# class_ab.net
KiCad netlist of a schematic drawn in EAGLE
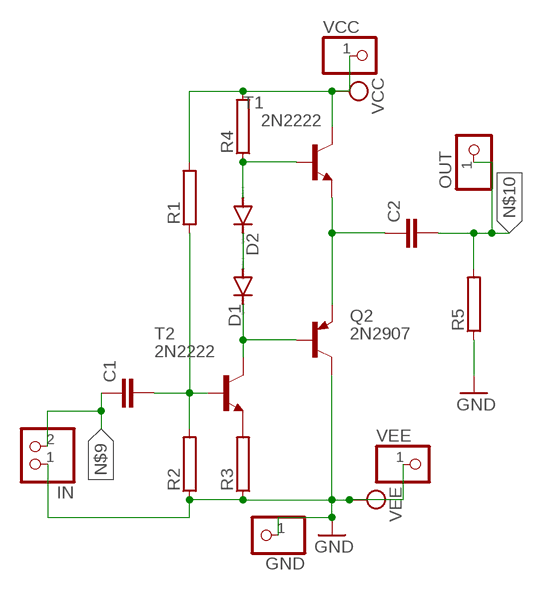
[diagram p0: schematic, sheet 1]

(export (version "E")
  (design (tool "Eeschema 10.0.6"))
  (components
    (comp (ref "C1")
      (value "C2,5-3")
      (footprint "eagle-import:C2.5-3")
      (libsource (lib "eagle-import") (part "C2,5-3"))
    )
    (comp (ref "C2")
      (value "C2,5-3")
      (footprint "eagle-import:C2.5-3")
      (libsource (lib "eagle-import") (part "C2,5-3"))
    )
    (comp (ref "D1")
      (value "1N4148DO35-7")
      (footprint "eagle-import:DO35-7")
      (libsource (lib "eagle-import") (part "1N4148DO35-7"))
    )
    (comp (ref "D2")
      (value "1N4148DO35-7")
      (footprint "eagle-import:DO35-7")
      (libsource (lib "eagle-import") (part "1N4148DO35-7"))
    )
    (comp (ref "GND")
      (value "PINHD-1X1")
      (footprint "eagle-import:1X01")
      (libsource (lib "eagle-import") (part "PINHD-1X1"))
    )
    (comp (ref "IN")
      (value "PINHD-1X2")
      (footprint "eagle-import:1X02")
      (libsource (lib "eagle-import") (part "PINHD-1X2"))
    )
    (comp (ref "OUT")
      (value "PINHD-1X1")
      (footprint "eagle-import:1X01")
      (libsource (lib "eagle-import") (part "PINHD-1X1"))
    )
    (comp (ref "Q2")
      (value "2N2907")
      (footprint "eagle-import:TO18")
      (libsource (lib "eagle-import") (part "2N2907"))
    )
    (comp (ref "R1")
      (value "RAC01")
      (footprint "eagle-import:AC01")
      (libsource (lib "eagle-import") (part "RAC01"))
    )
    (comp (ref "R2")
      (value "RAC01")
      (footprint "eagle-import:AC01")
      (libsource (lib "eagle-import") (part "RAC01"))
    )
    (comp (ref "R3")
      (value "RAC01")
      (footprint "eagle-import:AC01")
      (libsource (lib "eagle-import") (part "RAC01"))
    )
    (comp (ref "R4")
      (value "RAC01")
      (footprint "eagle-import:AC01")
      (libsource (lib "eagle-import") (part "RAC01"))
    )
    (comp (ref "R5")
      (value "RAC01")
      (footprint "eagle-import:AC01")
      (libsource (lib "eagle-import") (part "RAC01"))
    )
    (comp (ref "T1")
      (value "2N2222")
      (footprint "eagle-import:TO18")
      (libsource (lib "eagle-import") (part "2N2222"))
    )
    (comp (ref "T2")
      (value "2N2222")
      (footprint "eagle-import:TO18")
      (libsource (lib "eagle-import") (part "2N2222"))
    )
    (comp (ref "VCC")
      (value "PINHD-1X1")
      (footprint "eagle-import:1X01")
      (libsource (lib "eagle-import") (part "PINHD-1X1"))
    )
    (comp (ref "VEE")
      (value "PINHD-1X1")
      (footprint "eagle-import:1X01")
      (libsource (lib "eagle-import") (part "PINHD-1X1"))
    )
  )
  (nets
    (net (code "1") (name "GND") (class "Default")
      (node (ref "GND") (pin "1") (pinfunction "1_1") (pintype "passive"))
      (node (ref "IN") (pin "1") (pinfunction "1_1") (pintype "passive"))
      (node (ref "Q2") (pin "3") (pinfunction "C_3") (pintype "passive"))
      (node (ref "R2") (pin "1") (pinfunction "1_1") (pintype "passive"))
      (node (ref "R3") (pin "1") (pinfunction "1_1") (pintype "passive"))
      (node (ref "R5") (pin "1") (pinfunction "1_1") (pintype "passive"))
      (node (ref "VEE") (pin "1") (pinfunction "1_1") (pintype "passive"))
    )
    (net (code "2") (name "N$9") (class "Default")
      (node (ref "C1") (pin "1") (pinfunction "1_1") (pintype "passive"))
      (node (ref "IN") (pin "2") (pinfunction "2_2") (pintype "passive"))
    )
    (net (code "3") (name "N$10") (class "Default")
      (node (ref "C2") (pin "2") (pinfunction "2_2") (pintype "passive"))
      (node (ref "OUT") (pin "1") (pinfunction "1_1") (pintype "passive"))
      (node (ref "R5") (pin "2") (pinfunction "2_2") (pintype "passive"))
    )
    (net (code "4") (name "Net-(D1-PadA)") (class "Default")
      (node (ref "D1") (pin "A") (pinfunction "A_A") (pintype "passive"))
      (node (ref "D2") (pin "C") (pinfunction "C_C") (pintype "passive"))
    )
    (net (code "5") (name "Net-(Q2-B)") (class "Default")
      (node (ref "D1") (pin "C") (pinfunction "C_C") (pintype "passive"))
      (node (ref "Q2") (pin "2") (pinfunction "B_2") (pintype "passive"))
      (node (ref "T2") (pin "3") (pinfunction "C_3") (pintype "passive"))
    )
    (net (code "6") (name "Net-(Q2-E)") (class "Default")
      (node (ref "C2") (pin "1") (pinfunction "1_1") (pintype "passive"))
      (node (ref "Q2") (pin "1") (pinfunction "E_1") (pintype "passive"))
      (node (ref "T1") (pin "1") (pinfunction "E_1") (pintype "passive"))
    )
    (net (code "7") (name "Net-(T1-B)") (class "Default")
      (node (ref "D2") (pin "A") (pinfunction "A_A") (pintype "passive"))
      (node (ref "R4") (pin "1") (pinfunction "1_1") (pintype "passive"))
      (node (ref "T1") (pin "2") (pinfunction "B_2") (pintype "passive"))
    )
    (net (code "8") (name "Net-(T2-B)") (class "Default")
      (node (ref "C1") (pin "2") (pinfunction "2_2") (pintype "passive"))
      (node (ref "R1") (pin "1") (pinfunction "1_1") (pintype "passive"))
      (node (ref "R2") (pin "2") (pinfunction "2_2") (pintype "passive"))
      (node (ref "T2") (pin "2") (pinfunction "B_2") (pintype "passive"))
    )
    (net (code "9") (name "Net-(T2-E)") (class "Default")
      (node (ref "R3") (pin "2") (pinfunction "2_2") (pintype "passive"))
      (node (ref "T2") (pin "1") (pinfunction "E_1") (pintype "passive"))
    )
    (net (code "10") (name "VCC") (class "Default")
      (node (ref "R1") (pin "2") (pinfunction "2_2") (pintype "passive"))
      (node (ref "R4") (pin "2") (pinfunction "2_2") (pintype "passive"))
      (node (ref "T1") (pin "3") (pinfunction "C_3") (pintype "passive"))
      (node (ref "VCC") (pin "1") (pinfunction "1_1") (pintype "passive"))
    )
  )
)
